# 2button_LED_parallel.net
KiCad netlist of a schematic drawn in EAGLE
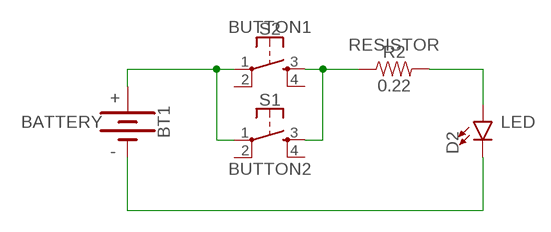
[diagram p0: schematic, sheet 1]

(export (version "E")
  (design (tool "Eeschema 10.0.6"))
  (components
    (comp (ref "BT1")
      (value "BATTERY-9V")
      (footprint "eagle-import:BATTCON_9V")
      (libsource (lib "eagle-import") (part "BATTERY-9V"))
    )
    (comp (ref "D2")
      (value "LED5MM")
      (footprint "eagle-import:LED_5MM")
      (libsource (lib "eagle-import") (part "LED5MM"))
    )
    (comp (ref "R2")
      (value "0.22")
      (footprint "eagle-import:0805")
      (libsource (lib "eagle-import") (part "0.22OHM-0805-1/4W-1%"))
    )
    (comp (ref "S1")
      (value "MOMENTARY-SWITCH-SPST-2-SMD-4.6X2.8MM")
      (footprint "eagle-import:TACTILE_SWITCH_SMD_4.6X2.8MM")
      (libsource (lib "eagle-import") (part "MOMENTARY-SWITCH-SPST-2-SMD-4.6X2.8MM"))
    )
    (comp (ref "S2")
      (value "MOMENTARY-SWITCH-SPST-2-SMD-4.6X2.8MM")
      (footprint "eagle-import:TACTILE_SWITCH_SMD_4.6X2.8MM")
      (libsource (lib "eagle-import") (part "MOMENTARY-SWITCH-SPST-2-SMD-4.6X2.8MM"))
    )
  )
  (nets
    (net (code "1") (name "Net-(BT1-Pad+)") (class "Default")
      (node (ref "BT1") (pin "+") (pinfunction "+_+") (pintype "power_in"))
      (node (ref "S1") (pin "1") (pinfunction "1_1") (pintype "passive"))
      (node (ref "S2") (pin "1") (pinfunction "1_1") (pintype "passive"))
    )
    (net (code "2") (name "Net-(D2-C)") (class "Default")
      (node (ref "BT1") (pin "-") (pinfunction "-_-") (pintype "power_in"))
      (node (ref "D2") (pin "K") (pinfunction "C_K") (pintype "passive"))
    )
    (net (code "3") (name "Net-(D2-PadA)") (class "Default")
      (node (ref "D2") (pin "A") (pinfunction "A_A") (pintype "passive"))
      (node (ref "R2") (pin "2") (pinfunction "2_2") (pintype "passive"))
    )
    (net (code "4") (name "Net-(R2-Pad1)") (class "Default")
      (node (ref "R2") (pin "1") (pinfunction "1_1") (pintype "passive"))
      (node (ref "S1") (pin "3") (pinfunction "3_3") (pintype "passive"))
      (node (ref "S2") (pin "3") (pinfunction "3_3") (pintype "passive"))
    )
    (net (code "5") (name "unconnected-(S1-Pad2)") (class "Default")
      (node (ref "S1") (pin "2") (pinfunction "2_2") (pintype "passive"))
    )
    (net (code "6") (name "unconnected-(S1-Pad4)") (class "Default")
      (node (ref "S1") (pin "4") (pinfunction "4_4") (pintype "passive"))
    )
    (net (code "7") (name "unconnected-(S2-Pad2)") (class "Default")
      (node (ref "S2") (pin "2") (pinfunction "2_2") (pintype "passive"))
    )
    (net (code "8") (name "unconnected-(S2-Pad4)") (class "Default")
      (node (ref "S2") (pin "4") (pinfunction "4_4") (pintype "passive"))
    )
  )
)
